# I2C_Subsystems.net
KiCad netlist of a schematic drawn in Altium Designer
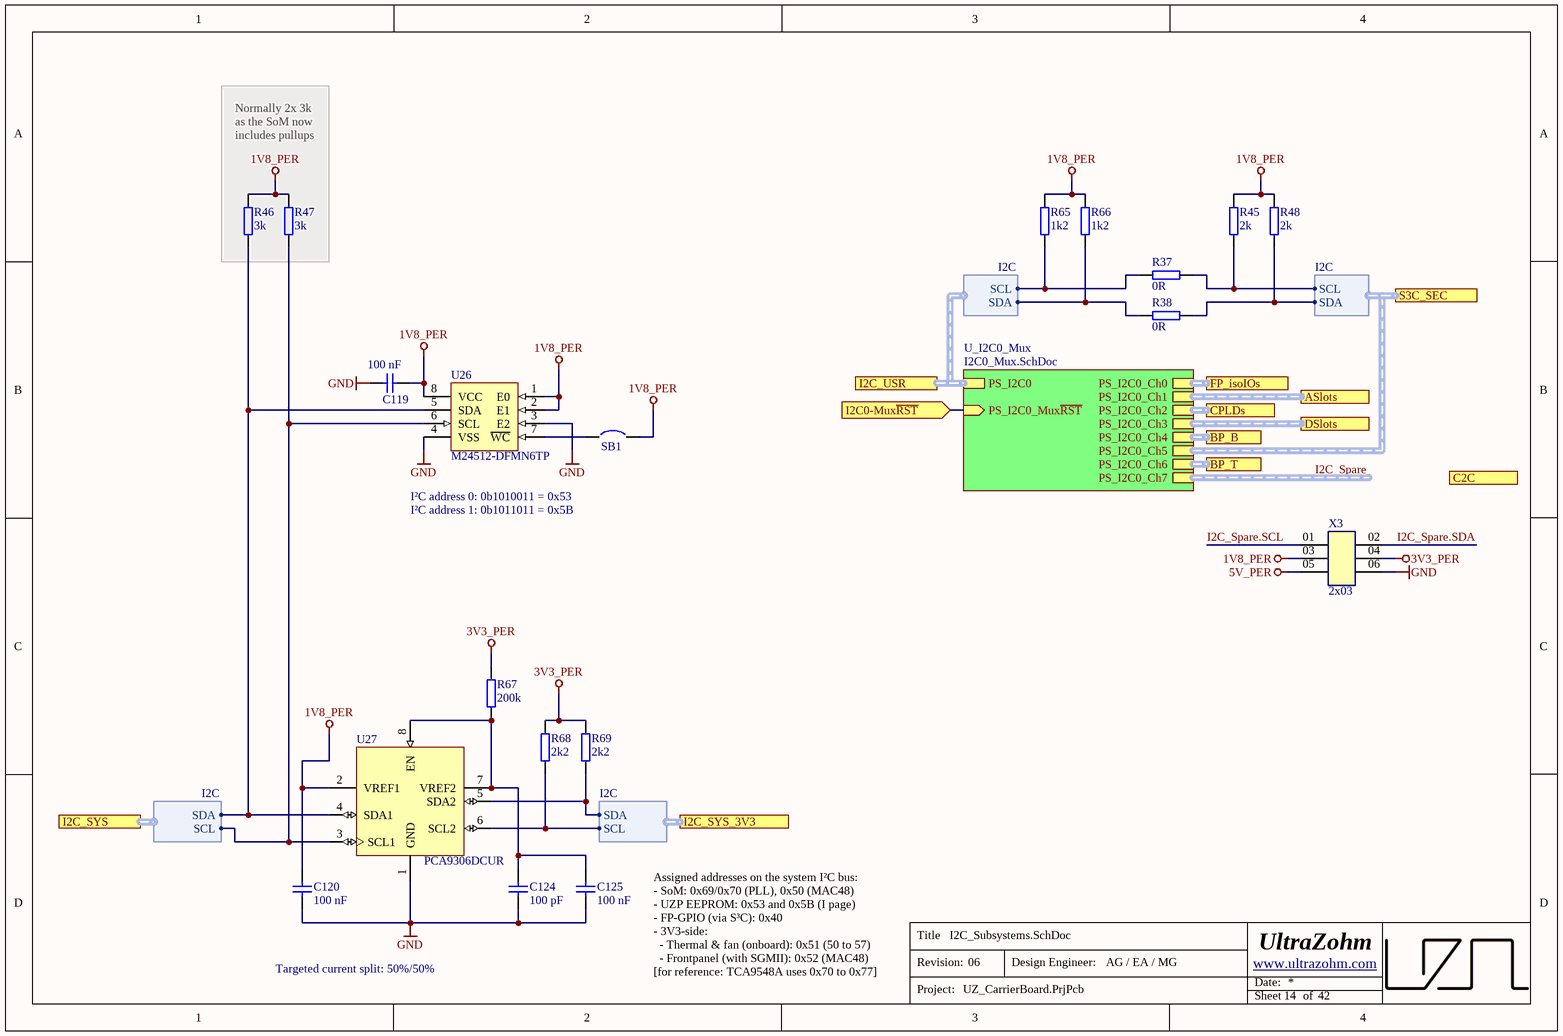
[diagram p0: I2C_Subsystems.SchDoc]

(export (version "E")
  (design (tool "Eeschema 10.0.6"))
  (components
    (comp (ref "C119")
      (value "100 nF")
      (footprint "C_0603_TE")
      (description "Generic capacitor")
      (fields
        (field (name "MANUFACTURER PART NUMBER") "UZgen_C_0603_100nF_50V_X7R")
        (field (name "MANUFACTURER") "UZgen")
        (field (name "CREATED FROM") "AGeiger")
      )
      (libsource (lib "user") (part "CAP-NP"))
    )
    (comp (ref "C120")
      (value "100 nF")
      (footprint "C_0603_TE")
      (description "Generic capacitor")
      (fields
        (field (name "MANUFACTURER PART NUMBER") "UZgen_C_0603_100nF_50V_X7R")
        (field (name "MANUFACTURER") "UZgen")
        (field (name "CREATED FROM") "AGeiger")
      )
      (libsource (lib "user") (part "CAP-NP"))
    )
    (comp (ref "C124")
      (value "100 pF")
      (footprint "C_0603_TE")
      (description "Generic capacitor")
      (fields
        (field (name "MANUFACTURER PART NUMBER") "UZgen_C_0603_100pF_50V_X7R")
        (field (name "MANUFACTURER") "UZgen")
        (field (name "CREATED FROM") "UZgenTool")
      )
      (libsource (lib "user") (part "CAP-NP"))
    )
    (comp (ref "C125")
      (value "100 nF")
      (footprint "C_0603_TE")
      (description "Generic capacitor")
      (fields
        (field (name "MANUFACTURER PART NUMBER") "UZgen_C_0603_100nF_50V_X7R")
        (field (name "MANUFACTURER") "UZgen")
        (field (name "CREATED FROM") "AGeiger")
      )
      (libsource (lib "user") (part "CAP-NP"))
    )
    (comp (ref "R37")
      (value "0R")
      (footprint "R_0603_TE")
      (description "Generic resistor")
      (fields
        (field (name "MANUFACTURER PART NUMBER") "UZgen_R_0603_0R")
        (field (name "MANUFACTURER") "UZgen")
        (field (name "CREATED FROM") "UZgenTool")
      )
      (libsource (lib "user") (part "RES"))
    )
    (comp (ref "R38")
      (value "0R")
      (footprint "R_0603_TE")
      (description "Generic resistor")
      (fields
        (field (name "MANUFACTURER PART NUMBER") "UZgen_R_0603_0R")
        (field (name "MANUFACTURER") "UZgen")
        (field (name "CREATED FROM") "UZgenTool")
      )
      (libsource (lib "user") (part "RES"))
    )
    (comp (ref "R45")
      (value "2k")
      (footprint "R_0603_TE")
      (description "Generic resistor")
      (fields
        (field (name "MANUFACTURER PART NUMBER") "UZgen_R_0603_2k")
        (field (name "MANUFACTURER") "UZgen")
        (field (name "CREATED FROM") "UZgenTool")
      )
      (libsource (lib "user") (part "RES"))
    )
    (comp (ref "R46")
      (value "3k")
      (footprint "R_0603_TE")
      (description "Generic resistor")
      (fields
        (field (name "MANUFACTURER PART NUMBER") "UZgen_R_0603_3k")
        (field (name "MANUFACTURER") "UZgen")
        (field (name "CREATED FROM") "UZgenTool")
      )
      (libsource (lib "user") (part "RES"))
    )
    (comp (ref "R47")
      (value "3k")
      (footprint "R_0603_TE")
      (description "Generic resistor")
      (fields
        (field (name "MANUFACTURER PART NUMBER") "UZgen_R_0603_3k")
        (field (name "MANUFACTURER") "UZgen")
        (field (name "CREATED FROM") "UZgenTool")
      )
      (libsource (lib "user") (part "RES"))
    )
    (comp (ref "R48")
      (value "2k")
      (footprint "R_0603_TE")
      (description "Generic resistor")
      (fields
        (field (name "MANUFACTURER PART NUMBER") "UZgen_R_0603_2k")
        (field (name "MANUFACTURER") "UZgen")
        (field (name "CREATED FROM") "UZgenTool")
      )
      (libsource (lib "user") (part "RES"))
    )
    (comp (ref "R65")
      (value "1k2")
      (footprint "R_0603_TE")
      (description "Generic resistor")
      (fields
        (field (name "MANUFACTURER PART NUMBER") "UZgen_R_0603_1k2")
        (field (name "MANUFACTURER") "UZgen")
        (field (name "CREATED FROM") "UZgenTool")
      )
      (libsource (lib "user") (part "RES"))
    )
    (comp (ref "R66")
      (value "1k2")
      (footprint "R_0603_TE")
      (description "Generic resistor")
      (fields
        (field (name "MANUFACTURER PART NUMBER") "UZgen_R_0603_1k2")
        (field (name "MANUFACTURER") "UZgen")
        (field (name "CREATED FROM") "UZgenTool")
      )
      (libsource (lib "user") (part "RES"))
    )
    (comp (ref "R67")
      (value "200k")
      (footprint "R_0603_TE")
      (description "Generic resistor")
      (fields
        (field (name "MANUFACTURER PART NUMBER") "UZgen_R_0603_200k")
        (field (name "MANUFACTURER") "UZgen")
        (field (name "CREATED FROM") "UZgenTool")
      )
      (libsource (lib "user") (part "RES"))
    )
    (comp (ref "R68")
      (value "2k2")
      (footprint "R_0603_TE")
      (description "Generic resistor")
      (fields
        (field (name "MANUFACTURER PART NUMBER") "UZgen_R_0603_2k2")
        (field (name "MANUFACTURER") "UZgen")
        (field (name "CREATED FROM") "UZgenTool")
      )
      (libsource (lib "user") (part "RES"))
    )
    (comp (ref "R69")
      (value "2k2")
      (footprint "R_0603_TE")
      (description "Generic resistor")
      (fields
        (field (name "MANUFACTURER PART NUMBER") "UZgen_R_0603_2k2")
        (field (name "MANUFACTURER") "UZgen")
        (field (name "CREATED FROM") "UZgenTool")
      )
      (libsource (lib "user") (part "RES"))
    )
    (comp (ref "SB1")
      (value "Solder Bump 0603")
      (footprint "SB_0603")
      (fields (field (name "CREATED FROM") "AGeiger"))
      (libsource (lib "user") (part "Solder_Bump"))
    )
    (comp (ref "U26")
      (value "M24512-DFMN6TP")
      (footprint "D0008A_N")
      (description "512Kbit 1MHz I2C SOP-8 EEPROM ROHS")
      (fields
        (field (name "MANUFACTURER") "STMicroelectronics")
        (field (name "LCSC PART NUMBER") "C222090")
        (field (name "CREATED FROM") "FRosner")
      )
      (libsource (lib "user") (part "M24256"))
    )
    (comp (ref "U27")
      (value "PCA9306DCUR")
      (footprint "FP-DCU0008A-IPC_B")
      (description "Translation - Voltage Levels Dual BiDir I2C-Bus & SMBus Vltg Lvl-Trans")
      (fields
        (field (name "MANUFACTURER") "Texas Instruments")
        (field (name "LCSC PART NUMBER") "C33196")
        (field (name "CREATED FROM") "FRosner")
      )
      (libsource (lib "user") (part "PCA9306"))
    )
    (comp (ref "X3")
      (value "PH 0.1\" SMD 2x03")
      (footprint "TSM-103-01-L-DV")
      (description "0.1\" Double-row Pin Header, 90°-to-PCB SMD, 2x03 Pins, 250V, 3A")
      (fields
        (field (name "MANUFACTURER PART NUMBER") "UZgen_Conn_PinHead_2x03_SMD_100mil_90deg")
        (field (name "MANUFACTURER") "UZgen")
        (field (name "PIN LAYOUT") "2x03")
        (field (name "CREATED FROM") "UZgenTool")
      )
      (libsource (lib "user") (part "PinHeader_2x03"))
    )
  )
  (nets
    (net (code "18") (name "/I2C_Spare.SCL") (class "Default")
      (node (ref "X3") (pin "01") (pinfunction "01_01") (pintype "passive"))
    )
    (net (code "19") (name "/I2C_Spare.SDA") (class "Default")
      (node (ref "X3") (pin "02") (pinfunction "02_02") (pintype "passive"))
    )
    (net (code "22") (name "1V8_PER") (class "Default")
      (node (ref "C119") (pin "2") (pinfunction "2_2") (pintype "passive"))
      (node (ref "C120") (pin "2") (pinfunction "2_2") (pintype "passive"))
      (node (ref "R45") (pin "2") (pinfunction "2_2") (pintype "passive"))
      (node (ref "R46") (pin "2") (pinfunction "2_2") (pintype "passive"))
      (node (ref "R47") (pin "2") (pinfunction "2_2") (pintype "passive"))
      (node (ref "R48") (pin "2") (pinfunction "2_2") (pintype "passive"))
      (node (ref "R65") (pin "2") (pinfunction "2_2") (pintype "passive"))
      (node (ref "R66") (pin "2") (pinfunction "2_2") (pintype "passive"))
      (node (ref "SB1") (pin "2") (pinfunction "2_2") (pintype "passive"))
      (node (ref "U26") (pin "1") (pinfunction "E0_1") (pintype "input"))
      (node (ref "U26") (pin "2") (pinfunction "E1_2") (pintype "input"))
      (node (ref "U26") (pin "8") (pinfunction "VCC_8") (pintype "power_in"))
      (node (ref "U27") (pin "2") (pinfunction "VREF1_2") (pintype "power_in"))
      (node (ref "X3") (pin "03") (pinfunction "03_03") (pintype "passive"))
    )
    (net (code "23") (name "3V3_PER") (class "Default")
      (node (ref "R67") (pin "2") (pinfunction "2_2") (pintype "passive"))
      (node (ref "R68") (pin "2") (pinfunction "2_2") (pintype "passive"))
      (node (ref "R69") (pin "2") (pinfunction "2_2") (pintype "passive"))
      (node (ref "X3") (pin "04") (pinfunction "04_04") (pintype "passive"))
    )
    (net (code "24") (name "5V_PER") (class "Default")
      (node (ref "X3") (pin "05") (pinfunction "05_05") (pintype "passive"))
    )
    (net (code "25") (name "GND") (class "Default")
      (node (ref "C119") (pin "1") (pinfunction "1_1") (pintype "passive"))
      (node (ref "C120") (pin "1") (pinfunction "1_1") (pintype "passive"))
      (node (ref "C124") (pin "1") (pinfunction "1_1") (pintype "passive"))
      (node (ref "C125") (pin "1") (pinfunction "1_1") (pintype "passive"))
      (node (ref "U26") (pin "3") (pinfunction "E2_3") (pintype "input"))
      (node (ref "U26") (pin "4") (pinfunction "VSS_4") (pintype "power_in"))
      (node (ref "U27") (pin "1") (pinfunction "GND_1") (pintype "power_in"))
      (node (ref "X3") (pin "06") (pinfunction "06_06") (pintype "passive"))
    )
    (net (code "26") (name "Net-(R37-Pad1)") (class "Default")
      (node (ref "R37") (pin "1") (pinfunction "1_1") (pintype "passive"))
      (node (ref "R65") (pin "1") (pinfunction "1_1") (pintype "passive"))
    )
    (net (code "27") (name "Net-(R37-Pad2)") (class "Default")
      (node (ref "R37") (pin "2") (pinfunction "2_2") (pintype "passive"))
      (node (ref "R45") (pin "1") (pinfunction "1_1") (pintype "passive"))
    )
    (net (code "28") (name "Net-(R38-Pad1)") (class "Default")
      (node (ref "R38") (pin "1") (pinfunction "1_1") (pintype "passive"))
      (node (ref "R66") (pin "1") (pinfunction "1_1") (pintype "passive"))
    )
    (net (code "29") (name "Net-(R38-Pad2)") (class "Default")
      (node (ref "R38") (pin "2") (pinfunction "2_2") (pintype "passive"))
      (node (ref "R48") (pin "1") (pinfunction "1_1") (pintype "passive"))
    )
    (net (code "30") (name "Net-(U26-SCL)") (class "Default")
      (node (ref "R47") (pin "1") (pinfunction "1_1") (pintype "passive"))
      (node (ref "U26") (pin "6") (pinfunction "SCL_6") (pintype "input"))
      (node (ref "U27") (pin "3") (pinfunction "SCL1_3") (pintype "bidirectional"))
    )
    (net (code "31") (name "Net-(U26-SDA)") (class "Default")
      (node (ref "R46") (pin "1") (pinfunction "1_1") (pintype "passive"))
      (node (ref "U26") (pin "5") (pinfunction "SDA_5") (pintype "open_collector"))
      (node (ref "U27") (pin "4") (pinfunction "SDA1_4") (pintype "bidirectional"))
    )
    (net (code "32") (name "Net-(U26-~{WC})") (class "Default")
      (node (ref "SB1") (pin "1") (pinfunction "1_1") (pintype "passive"))
      (node (ref "U26") (pin "7") (pinfunction "~{WC}_7") (pintype "input"))
    )
    (net (code "33") (name "Net-(U27-EN)") (class "Default")
      (node (ref "C124") (pin "2") (pinfunction "2_2") (pintype "passive"))
      (node (ref "C125") (pin "2") (pinfunction "2_2") (pintype "passive"))
      (node (ref "R67") (pin "1") (pinfunction "1_1") (pintype "passive"))
      (node (ref "U27") (pin "7") (pinfunction "VREF2_7") (pintype "power_in"))
      (node (ref "U27") (pin "8") (pinfunction "EN_8") (pintype "input"))
    )
    (net (code "34") (name "Net-(U27-SCL2)") (class "Default")
      (node (ref "R68") (pin "1") (pinfunction "1_1") (pintype "passive"))
      (node (ref "U27") (pin "6") (pinfunction "SCL2_6") (pintype "bidirectional"))
    )
    (net (code "35") (name "Net-(U27-SDA2)") (class "Default")
      (node (ref "R69") (pin "1") (pinfunction "1_1") (pintype "passive"))
      (node (ref "U27") (pin "5") (pinfunction "SDA2_5") (pintype "bidirectional"))
    )
  )
)
